# INPUT.net
KiCad netlist of a schematic drawn in Altium Designer
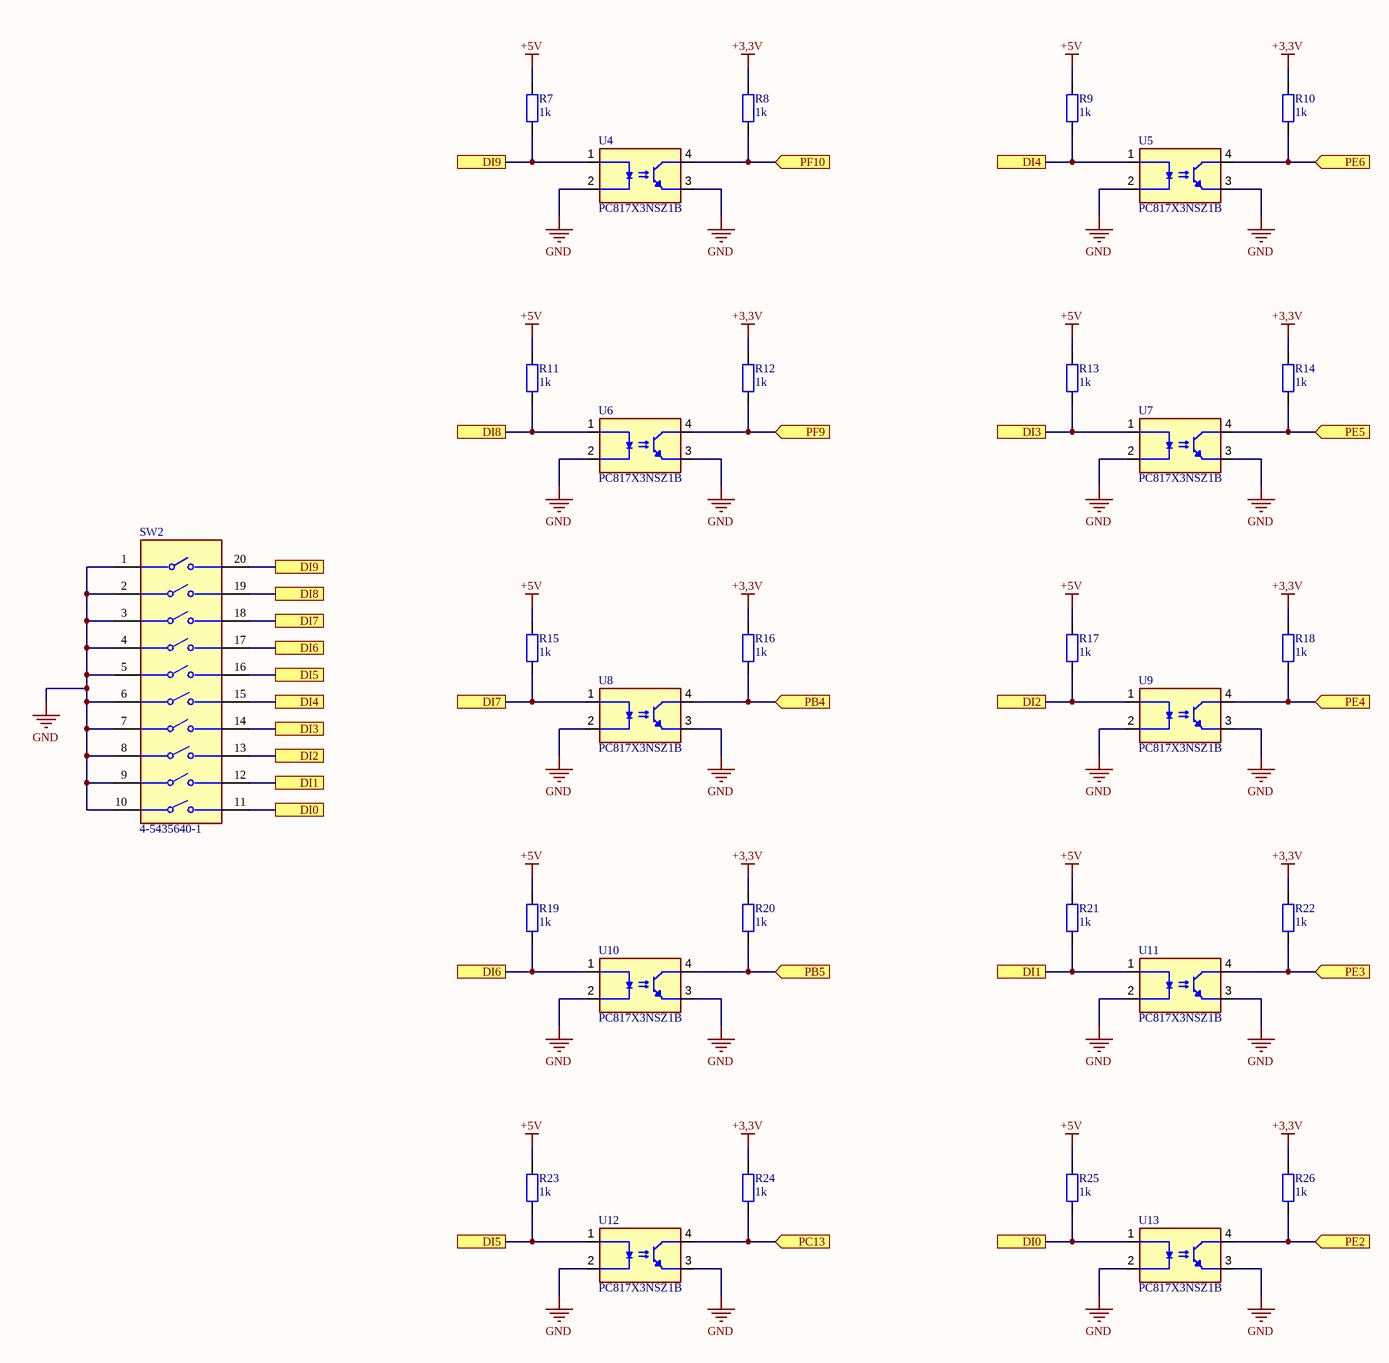
[diagram p0: INPUT.SchDoc]

(export (version "E")
  (design (tool "Eeschema 10.0.6"))
  (components
    (comp (ref "R7")
      (value "1k")
      (footprint "tro smd 0603")
      (description "RES")
      (libsource (lib "AUSB") (part "Tro 0603 1% 10k"))
    )
    (comp (ref "R8")
      (value "1k")
      (footprint "tro smd 0603")
      (description "RES")
      (libsource (lib "AUSB") (part "Tro 0603 1% 10k"))
    )
    (comp (ref "R9")
      (value "1k")
      (footprint "tro smd 0603")
      (description "RES")
      (libsource (lib "AUSB") (part "Tro 0603 1% 10k"))
    )
    (comp (ref "R10")
      (value "1k")
      (footprint "tro smd 0603")
      (description "RES")
      (libsource (lib "AUSB") (part "Tro 0603 1% 10k"))
    )
    (comp (ref "R11")
      (value "1k")
      (footprint "tro smd 0603")
      (description "RES")
      (libsource (lib "AUSB") (part "Tro 0603 1% 10k"))
    )
    (comp (ref "R12")
      (value "1k")
      (footprint "tro smd 0603")
      (description "RES")
      (libsource (lib "AUSB") (part "Tro 0603 1% 10k"))
    )
    (comp (ref "R13")
      (value "1k")
      (footprint "tro smd 0603")
      (description "RES")
      (libsource (lib "AUSB") (part "Tro 0603 1% 10k"))
    )
    (comp (ref "R14")
      (value "1k")
      (footprint "tro smd 0603")
      (description "RES")
      (libsource (lib "AUSB") (part "Tro 0603 1% 10k"))
    )
    (comp (ref "R15")
      (value "1k")
      (footprint "tro smd 0603")
      (description "RES")
      (libsource (lib "AUSB") (part "Tro 0603 1% 10k"))
    )
    (comp (ref "R16")
      (value "1k")
      (footprint "tro smd 0603")
      (description "RES")
      (libsource (lib "AUSB") (part "Tro 0603 1% 10k"))
    )
    (comp (ref "R17")
      (value "1k")
      (footprint "tro smd 0603")
      (description "RES")
      (libsource (lib "AUSB") (part "Tro 0603 1% 10k"))
    )
    (comp (ref "R18")
      (value "1k")
      (footprint "tro smd 0603")
      (description "RES")
      (libsource (lib "AUSB") (part "Tro 0603 1% 10k"))
    )
    (comp (ref "R19")
      (value "1k")
      (footprint "tro smd 0603")
      (description "RES")
      (libsource (lib "AUSB") (part "Tro 0603 1% 10k"))
    )
    (comp (ref "R20")
      (value "1k")
      (footprint "tro smd 0603")
      (description "RES")
      (libsource (lib "AUSB") (part "Tro 0603 1% 10k"))
    )
    (comp (ref "R21")
      (value "1k")
      (footprint "tro smd 0603")
      (description "RES")
      (libsource (lib "AUSB") (part "Tro 0603 1% 10k"))
    )
    (comp (ref "R22")
      (value "1k")
      (footprint "tro smd 0603")
      (description "RES")
      (libsource (lib "AUSB") (part "Tro 0603 1% 10k"))
    )
    (comp (ref "R23")
      (value "1k")
      (footprint "tro smd 0603")
      (description "RES")
      (libsource (lib "AUSB") (part "Tro 0603 1% 10k"))
    )
    (comp (ref "R24")
      (value "1k")
      (footprint "tro smd 0603")
      (description "RES")
      (libsource (lib "AUSB") (part "Tro 0603 1% 10k"))
    )
    (comp (ref "R25")
      (value "1k")
      (footprint "tro smd 0603")
      (description "RES")
      (libsource (lib "AUSB") (part "Tro 0603 1% 10k"))
    )
    (comp (ref "R26")
      (value "1k")
      (footprint "tro smd 0603")
      (description "RES")
      (libsource (lib "AUSB") (part "Tro 0603 1% 10k"))
    )
    (comp (ref "SW2")
      (value "4-5435640-1")
      (footprint "FP-4-5435640-1-MFG")
      (description "SWITCH ROCKER DIP SPST 60MA 5V")
      (libsource (lib "10p_dip_switch") (part "CMP-03400-000018-1"))
    )
    (comp (ref "U4")
      (value "PC817X3NSZ1B")
      (footprint "DIP762W50P254L495H455Q4")
      (description "Optoisolator Transistor Output - 1 Channel 4-DIP")
      (fields (field (name "MF") "Sharp Microelectronics"))
      (libsource (lib "PC817X3NSZ1B") (part "PC817X3NSZ1B"))
    )
    (comp (ref "U5")
      (value "PC817X3NSZ1B")
      (footprint "DIP762W50P254L495H455Q4")
      (description "Optoisolator Transistor Output - 1 Channel 4-DIP")
      (fields (field (name "MF") "Sharp Microelectronics"))
      (libsource (lib "PC817X3NSZ1B") (part "PC817X3NSZ1B"))
    )
    (comp (ref "U6")
      (value "PC817X3NSZ1B")
      (footprint "DIP762W50P254L495H455Q4")
      (description "Optoisolator Transistor Output - 1 Channel 4-DIP")
      (fields (field (name "MF") "Sharp Microelectronics"))
      (libsource (lib "PC817X3NSZ1B") (part "PC817X3NSZ1B"))
    )
    (comp (ref "U7")
      (value "PC817X3NSZ1B")
      (footprint "DIP762W50P254L495H455Q4")
      (description "Optoisolator Transistor Output - 1 Channel 4-DIP")
      (fields (field (name "MF") "Sharp Microelectronics"))
      (libsource (lib "PC817X3NSZ1B") (part "PC817X3NSZ1B"))
    )
    (comp (ref "U8")
      (value "PC817X3NSZ1B")
      (footprint "DIP762W50P254L495H455Q4")
      (description "Optoisolator Transistor Output - 1 Channel 4-DIP")
      (fields (field (name "MF") "Sharp Microelectronics"))
      (libsource (lib "PC817X3NSZ1B") (part "PC817X3NSZ1B"))
    )
    (comp (ref "U9")
      (value "PC817X3NSZ1B")
      (footprint "DIP762W50P254L495H455Q4")
      (description "Optoisolator Transistor Output - 1 Channel 4-DIP")
      (fields (field (name "MF") "Sharp Microelectronics"))
      (libsource (lib "PC817X3NSZ1B") (part "PC817X3NSZ1B"))
    )
    (comp (ref "U10")
      (value "PC817X3NSZ1B")
      (footprint "DIP762W50P254L495H455Q4")
      (description "Optoisolator Transistor Output - 1 Channel 4-DIP")
      (fields (field (name "MF") "Sharp Microelectronics"))
      (libsource (lib "PC817X3NSZ1B") (part "PC817X3NSZ1B"))
    )
    (comp (ref "U11")
      (value "PC817X3NSZ1B")
      (footprint "DIP762W50P254L495H455Q4")
      (description "Optoisolator Transistor Output - 1 Channel 4-DIP")
      (fields (field (name "MF") "Sharp Microelectronics"))
      (libsource (lib "PC817X3NSZ1B") (part "PC817X3NSZ1B"))
    )
    (comp (ref "U12")
      (value "PC817X3NSZ1B")
      (footprint "DIP762W50P254L495H455Q4")
      (description "Optoisolator Transistor Output - 1 Channel 4-DIP")
      (fields (field (name "MF") "Sharp Microelectronics"))
      (libsource (lib "PC817X3NSZ1B") (part "PC817X3NSZ1B"))
    )
    (comp (ref "U13")
      (value "PC817X3NSZ1B")
      (footprint "DIP762W50P254L495H455Q4")
      (description "Optoisolator Transistor Output - 1 Channel 4-DIP")
      (fields (field (name "MF") "Sharp Microelectronics"))
      (libsource (lib "PC817X3NSZ1B") (part "PC817X3NSZ1B"))
    )
  )
  (nets
    (net (code "1") (name "+3,3V") (class "Default")
      (node (ref "R10") (pin "2") (pinfunction "2_2") (pintype "passive"))
      (node (ref "R12") (pin "2") (pinfunction "2_2") (pintype "passive"))
      (node (ref "R14") (pin "2") (pinfunction "2_2") (pintype "passive"))
      (node (ref "R16") (pin "2") (pinfunction "2_2") (pintype "passive"))
      (node (ref "R18") (pin "2") (pinfunction "2_2") (pintype "passive"))
      (node (ref "R20") (pin "2") (pinfunction "2_2") (pintype "passive"))
      (node (ref "R22") (pin "2") (pinfunction "2_2") (pintype "passive"))
      (node (ref "R24") (pin "2") (pinfunction "2_2") (pintype "passive"))
      (node (ref "R26") (pin "2") (pinfunction "2_2") (pintype "passive"))
      (node (ref "R8") (pin "2") (pinfunction "2_2") (pintype "passive"))
    )
    (net (code "2") (name "+5V") (class "Default")
      (node (ref "R11") (pin "2") (pinfunction "2_2") (pintype "passive"))
      (node (ref "R13") (pin "2") (pinfunction "2_2") (pintype "passive"))
      (node (ref "R15") (pin "2") (pinfunction "2_2") (pintype "passive"))
      (node (ref "R17") (pin "2") (pinfunction "2_2") (pintype "passive"))
      (node (ref "R19") (pin "2") (pinfunction "2_2") (pintype "passive"))
      (node (ref "R21") (pin "2") (pinfunction "2_2") (pintype "passive"))
      (node (ref "R23") (pin "2") (pinfunction "2_2") (pintype "passive"))
      (node (ref "R25") (pin "2") (pinfunction "2_2") (pintype "passive"))
      (node (ref "R7") (pin "2") (pinfunction "2_2") (pintype "passive"))
      (node (ref "R9") (pin "2") (pinfunction "2_2") (pintype "passive"))
    )
    (net (code "3") (name "/DI0") (class "Default")
      (node (ref "R25") (pin "1") (pinfunction "1_1") (pintype "passive"))
      (node (ref "SW2") (pin "11") (pinfunction "11_11") (pintype "passive"))
      (node (ref "U13") (pin "1") (pinfunction "ANODE_1") (pintype "passive"))
    )
    (net (code "4") (name "/DI1") (class "Default")
      (node (ref "R21") (pin "1") (pinfunction "1_1") (pintype "passive"))
      (node (ref "SW2") (pin "12") (pinfunction "12_12") (pintype "passive"))
      (node (ref "U11") (pin "1") (pinfunction "ANODE_1") (pintype "passive"))
    )
    (net (code "5") (name "/DI2") (class "Default")
      (node (ref "R17") (pin "1") (pinfunction "1_1") (pintype "passive"))
      (node (ref "SW2") (pin "13") (pinfunction "13_13") (pintype "passive"))
      (node (ref "U9") (pin "1") (pinfunction "ANODE_1") (pintype "passive"))
    )
    (net (code "6") (name "/DI3") (class "Default")
      (node (ref "R13") (pin "1") (pinfunction "1_1") (pintype "passive"))
      (node (ref "SW2") (pin "14") (pinfunction "14_14") (pintype "passive"))
      (node (ref "U7") (pin "1") (pinfunction "ANODE_1") (pintype "passive"))
    )
    (net (code "7") (name "/DI4") (class "Default")
      (node (ref "R9") (pin "1") (pinfunction "1_1") (pintype "passive"))
      (node (ref "SW2") (pin "15") (pinfunction "15_15") (pintype "passive"))
      (node (ref "U5") (pin "1") (pinfunction "ANODE_1") (pintype "passive"))
    )
    (net (code "8") (name "/DI5") (class "Default")
      (node (ref "R23") (pin "1") (pinfunction "1_1") (pintype "passive"))
      (node (ref "SW2") (pin "16") (pinfunction "16_16") (pintype "passive"))
      (node (ref "U12") (pin "1") (pinfunction "ANODE_1") (pintype "passive"))
    )
    (net (code "9") (name "/DI6") (class "Default")
      (node (ref "R19") (pin "1") (pinfunction "1_1") (pintype "passive"))
      (node (ref "SW2") (pin "17") (pinfunction "17_17") (pintype "passive"))
      (node (ref "U10") (pin "1") (pinfunction "ANODE_1") (pintype "passive"))
    )
    (net (code "10") (name "/DI7") (class "Default")
      (node (ref "R15") (pin "1") (pinfunction "1_1") (pintype "passive"))
      (node (ref "SW2") (pin "18") (pinfunction "18_18") (pintype "passive"))
      (node (ref "U8") (pin "1") (pinfunction "ANODE_1") (pintype "passive"))
    )
    (net (code "11") (name "/DI8") (class "Default")
      (node (ref "R11") (pin "1") (pinfunction "1_1") (pintype "passive"))
      (node (ref "SW2") (pin "19") (pinfunction "19_19") (pintype "passive"))
      (node (ref "U6") (pin "1") (pinfunction "ANODE_1") (pintype "passive"))
    )
    (net (code "12") (name "/DI9") (class "Default")
      (node (ref "R7") (pin "1") (pinfunction "1_1") (pintype "passive"))
      (node (ref "SW2") (pin "20") (pinfunction "20_20") (pintype "passive"))
      (node (ref "U4") (pin "1") (pinfunction "ANODE_1") (pintype "passive"))
    )
    (net (code "13") (name "/PB4") (class "Default")
      (node (ref "R16") (pin "1") (pinfunction "1_1") (pintype "passive"))
      (node (ref "U8") (pin "4") (pinfunction "COLLECTOR_4") (pintype "passive"))
    )
    (net (code "14") (name "/PB5") (class "Default")
      (node (ref "R20") (pin "1") (pinfunction "1_1") (pintype "passive"))
      (node (ref "U10") (pin "4") (pinfunction "COLLECTOR_4") (pintype "passive"))
    )
    (net (code "15") (name "/PC13") (class "Default")
      (node (ref "R24") (pin "1") (pinfunction "1_1") (pintype "passive"))
      (node (ref "U12") (pin "4") (pinfunction "COLLECTOR_4") (pintype "passive"))
    )
    (net (code "16") (name "/PE2") (class "Default")
      (node (ref "R26") (pin "1") (pinfunction "1_1") (pintype "passive"))
      (node (ref "U13") (pin "4") (pinfunction "COLLECTOR_4") (pintype "passive"))
    )
    (net (code "17") (name "/PE3") (class "Default")
      (node (ref "R22") (pin "1") (pinfunction "1_1") (pintype "passive"))
      (node (ref "U11") (pin "4") (pinfunction "COLLECTOR_4") (pintype "passive"))
    )
    (net (code "18") (name "/PE4") (class "Default")
      (node (ref "R18") (pin "1") (pinfunction "1_1") (pintype "passive"))
      (node (ref "U9") (pin "4") (pinfunction "COLLECTOR_4") (pintype "passive"))
    )
    (net (code "19") (name "/PE5") (class "Default")
      (node (ref "R14") (pin "1") (pinfunction "1_1") (pintype "passive"))
      (node (ref "U7") (pin "4") (pinfunction "COLLECTOR_4") (pintype "passive"))
    )
    (net (code "20") (name "/PE6") (class "Default")
      (node (ref "R10") (pin "1") (pinfunction "1_1") (pintype "passive"))
      (node (ref "U5") (pin "4") (pinfunction "COLLECTOR_4") (pintype "passive"))
    )
    (net (code "21") (name "/PF9") (class "Default")
      (node (ref "R12") (pin "1") (pinfunction "1_1") (pintype "passive"))
      (node (ref "U6") (pin "4") (pinfunction "COLLECTOR_4") (pintype "passive"))
    )
    (net (code "22") (name "/PF10") (class "Default")
      (node (ref "R8") (pin "1") (pinfunction "1_1") (pintype "passive"))
      (node (ref "U4") (pin "4") (pinfunction "COLLECTOR_4") (pintype "passive"))
    )
    (net (code "23") (name "GND") (class "Default")
      (node (ref "SW2") (pin "1") (pinfunction "1_1") (pintype "passive"))
      (node (ref "SW2") (pin "10") (pinfunction "10_10") (pintype "passive"))
      (node (ref "SW2") (pin "2") (pinfunction "2_2") (pintype "passive"))
      (node (ref "SW2") (pin "3") (pinfunction "3_3") (pintype "passive"))
      (node (ref "SW2") (pin "4") (pinfunction "4_4") (pintype "passive"))
      (node (ref "SW2") (pin "5") (pinfunction "5_5") (pintype "passive"))
      (node (ref "SW2") (pin "6") (pinfunction "6_6") (pintype "passive"))
      (node (ref "SW2") (pin "7") (pinfunction "7_7") (pintype "passive"))
      (node (ref "SW2") (pin "8") (pinfunction "8_8") (pintype "passive"))
      (node (ref "SW2") (pin "9") (pinfunction "9_9") (pintype "passive"))
      (node (ref "U10") (pin "2") (pinfunction "CATHODE_2") (pintype "passive"))
      (node (ref "U10") (pin "3") (pinfunction "EMITTER_3") (pintype "passive"))
      (node (ref "U11") (pin "2") (pinfunction "CATHODE_2") (pintype "passive"))
      (node (ref "U11") (pin "3") (pinfunction "EMITTER_3") (pintype "passive"))
      (node (ref "U12") (pin "2") (pinfunction "CATHODE_2") (pintype "passive"))
      (node (ref "U12") (pin "3") (pinfunction "EMITTER_3") (pintype "passive"))
      (node (ref "U13") (pin "2") (pinfunction "CATHODE_2") (pintype "passive"))
      (node (ref "U13") (pin "3") (pinfunction "EMITTER_3") (pintype "passive"))
      (node (ref "U4") (pin "2") (pinfunction "CATHODE_2") (pintype "passive"))
      (node (ref "U4") (pin "3") (pinfunction "EMITTER_3") (pintype "passive"))
      (node (ref "U5") (pin "2") (pinfunction "CATHODE_2") (pintype "passive"))
      (node (ref "U5") (pin "3") (pinfunction "EMITTER_3") (pintype "passive"))
      (node (ref "U6") (pin "2") (pinfunction "CATHODE_2") (pintype "passive"))
      (node (ref "U6") (pin "3") (pinfunction "EMITTER_3") (pintype "passive"))
      (node (ref "U7") (pin "2") (pinfunction "CATHODE_2") (pintype "passive"))
      (node (ref "U7") (pin "3") (pinfunction "EMITTER_3") (pintype "passive"))
      (node (ref "U8") (pin "2") (pinfunction "CATHODE_2") (pintype "passive"))
      (node (ref "U8") (pin "3") (pinfunction "EMITTER_3") (pintype "passive"))
      (node (ref "U9") (pin "2") (pinfunction "CATHODE_2") (pintype "passive"))
      (node (ref "U9") (pin "3") (pinfunction "EMITTER_3") (pintype "passive"))
    )
  )
)
